# HPF.net
KiCad netlist of a schematic drawn in Altium Designer
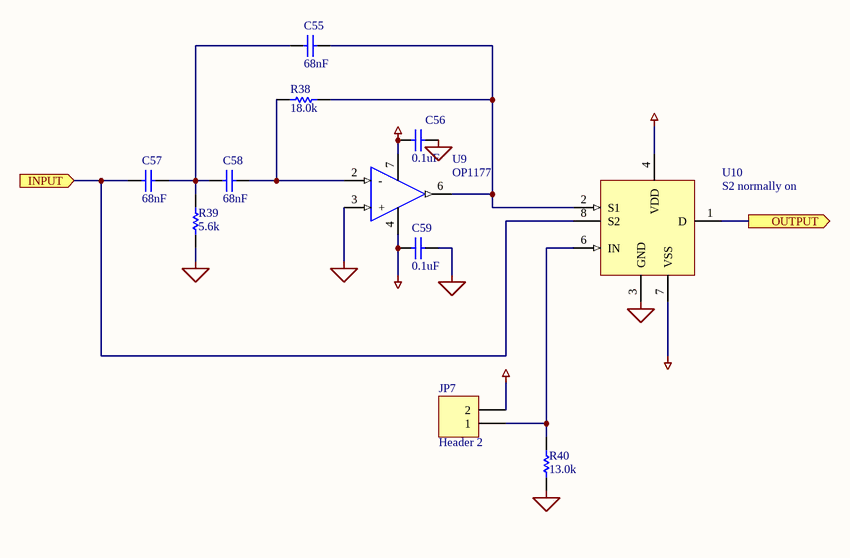
[diagram p0: HPF.SCHDOC]

(export (version "E")
  (design (tool "Eeschema 10.0.6"))
  (components
    (comp (ref "C55")
      (value "68nF")
      (footprint "CC3216-1206")
      (description "Capacitor")
      (fields
        (field (name "MANUFACTURER") "Generic Components")
        (field (name "Comment") "Cap")
        (field (name "PUBLISHER") "Altium Limited")
      )
      (libsource (lib "Miscellaneous Devices") (part "Cap"))
    )
    (comp (ref "C56")
      (value "0.1uF")
      (footprint "CC1608-0603")
      (description "Capacitor")
      (fields
        (field (name "MANUFACTURER") "Generic Components")
        (field (name "Comment") "Cap")
        (field (name "PUBLISHER") "Altium Limited")
      )
      (libsource (lib "Miscellaneous Devices") (part "Cap"))
    )
    (comp (ref "C57")
      (value "68nF")
      (footprint "CC3216-1206")
      (description "Capacitor")
      (fields
        (field (name "MANUFACTURER") "Generic Components")
        (field (name "Comment") "Cap")
        (field (name "PUBLISHER") "Altium Limited")
      )
      (libsource (lib "Miscellaneous Devices") (part "Cap"))
    )
    (comp (ref "C58")
      (value "68nF")
      (footprint "CC3216-1206")
      (description "Capacitor")
      (fields
        (field (name "MANUFACTURER") "Generic Components")
        (field (name "Comment") "Cap")
        (field (name "PUBLISHER") "Altium Limited")
      )
      (libsource (lib "Miscellaneous Devices") (part "Cap"))
    )
    (comp (ref "C59")
      (value "0.1uF")
      (footprint "CC1608-0603")
      (description "Capacitor")
      (fields
        (field (name "MANUFACTURER") "Generic Components")
        (field (name "Comment") "Cap")
        (field (name "PUBLISHER") "Altium Limited")
      )
      (libsource (lib "Miscellaneous Devices") (part "Cap"))
    )
    (comp (ref "JP7")
      (value "Header 2")
      (footprint "HDR1X2")
      (description "Header, 2-Pin")
      (fields (field (name "MANUFACTURER") "Generic Components") (field (name "PUBLISHER") "Altium Limited"))
      (libsource (lib "Miscellaneous Connectors") (part "Header 2"))
    )
    (comp (ref "R38")
      (value "18.0k")
      (footprint "CC2012-0805")
      (description "Resistor")
      (fields
        (field (name "MANUFACTURER") "Generic Components")
        (field (name "Comment") "Res1")
        (field (name "PUBLISHER") "Altium Limited")
      )
      (libsource (lib "Miscellaneous Devices") (part "Res1"))
    )
    (comp (ref "R39")
      (value "5.6k")
      (footprint "CC2012-0805")
      (description "Resistor")
      (fields
        (field (name "MANUFACTURER") "Generic Components")
        (field (name "Comment") "Res1")
        (field (name "PUBLISHER") "Altium Limited")
      )
      (libsource (lib "Miscellaneous Devices") (part "Res1"))
    )
    (comp (ref "R40")
      (value "13.0k")
      (footprint "CC2012-0805")
      (description "Resistor")
      (fields
        (field (name "MANUFACTURER") "Generic Components")
        (field (name "Comment") "Res1")
        (field (name "PUBLISHER") "Altium Limited")
      )
      (libsource (lib "Miscellaneous Devices") (part "Res1"))
    )
    (comp (ref "U9")
      (value "OP1177")
      (footprint "SO-G8/X.6")
      (description "AD Precision Low Noise, Low Input Bias Current Operational Amplifier")
      (libsource (lib "My devices") (part "OP1177"))
    )
    (comp (ref "U10")
      (value "S2 normally on")
      (footprint "MSOP8")
      (description "Low RON SPDT Switch")
      (libsource (lib "My devices") (part "ADG619"))
    )
  )
  (nets
    (net (code "1") (name "/INPUT") (class "Default")
      (node (ref "C57") (pin "2") (pinfunction "2_2") (pintype "passive"))
      (node (ref "U10") (pin "8") (pinfunction "S2_8") (pintype "passive"))
    )
    (net (code "2") (name "/OUTPUT") (class "Default")
      (node (ref "U10") (pin "1") (pinfunction "D_1") (pintype "passive"))
    )
    (net (code "3") (name "AGND") (class "Default")
      (node (ref "C56") (pin "2") (pinfunction "2_2") (pintype "passive"))
      (node (ref "C59") (pin "2") (pinfunction "2_2") (pintype "passive"))
      (node (ref "R39") (pin "1") (pinfunction "1_1") (pintype "passive"))
      (node (ref "R40") (pin "1") (pinfunction "1_1") (pintype "passive"))
      (node (ref "U10") (pin "3") (pinfunction "GND_3") (pintype "power_in"))
      (node (ref "U9") (pin "3") (pinfunction "+_3") (pintype "input"))
    )
    (net (code "4") (name "AVDD") (class "Default")
      (node (ref "C56") (pin "1") (pinfunction "1_1") (pintype "passive"))
      (node (ref "JP7") (pin "2") (pinfunction "2_2") (pintype "passive"))
      (node (ref "U10") (pin "4") (pinfunction "VDD_4") (pintype "power_in"))
      (node (ref "U9") (pin "7") (pinfunction "+Vs_7") (pintype "power_in"))
    )
    (net (code "5") (name "AVSS") (class "Default")
      (node (ref "C59") (pin "1") (pinfunction "1_1") (pintype "passive"))
      (node (ref "U10") (pin "7") (pinfunction "VSS_7") (pintype "power_in"))
      (node (ref "U9") (pin "4") (pinfunction "-Vs_4") (pintype "power_in"))
    )
    (net (code "6") (name "Net-(C55-Pad2)") (class "Default")
      (node (ref "C55") (pin "2") (pinfunction "2_2") (pintype "passive"))
      (node (ref "C57") (pin "1") (pinfunction "1_1") (pintype "passive"))
      (node (ref "C58") (pin "2") (pinfunction "2_2") (pintype "passive"))
      (node (ref "R39") (pin "2") (pinfunction "2_2") (pintype "passive"))
    )
    (net (code "7") (name "Net-(U9--)") (class "Default")
      (node (ref "C58") (pin "1") (pinfunction "1_1") (pintype "passive"))
      (node (ref "R38") (pin "2") (pinfunction "2_2") (pintype "passive"))
      (node (ref "U9") (pin "2") (pinfunction "-_2") (pintype "input"))
    )
    (net (code "8") (name "Net-(U10-IN)") (class "Default")
      (node (ref "JP7") (pin "1") (pinfunction "1_1") (pintype "passive"))
      (node (ref "R40") (pin "2") (pinfunction "2_2") (pintype "passive"))
      (node (ref "U10") (pin "6") (pinfunction "IN_6") (pintype "input"))
    )
    (net (code "9") (name "Net-(U10-S1)") (class "Default")
      (node (ref "C55") (pin "1") (pinfunction "1_1") (pintype "passive"))
      (node (ref "R38") (pin "1") (pinfunction "1_1") (pintype "passive"))
      (node (ref "U10") (pin "2") (pinfunction "S1_2") (pintype "input"))
      (node (ref "U9") (pin "6") (pinfunction "Out_6") (pintype "output"))
    )
  )
)
